# Sheet2_Lab08.net
KiCad netlist of a schematic drawn in Altium Designer
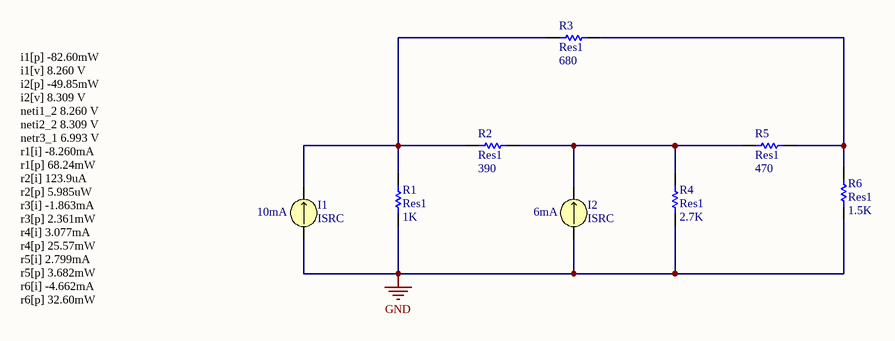
[diagram p0: Sheet2_Lab08.SchDoc]

(export (version "E")
  (design (tool "Eeschema 10.0.6"))
  (components
    (comp (ref "I1")
      (value "ISRC")
      (description "Current Source")
      (fields (field (name "ALTIUM_VALUE") "10mA") (field (name "PUBLISHER") "Altium Limited"))
      (libsource (lib "Simulation Sources") (part "ISRC"))
    )
    (comp (ref "I2")
      (value "ISRC")
      (description "Current Source")
      (fields (field (name "ALTIUM_VALUE") "6mA") (field (name "PUBLISHER") "Altium Limited"))
      (libsource (lib "Simulation Sources") (part "ISRC"))
    )
    (comp (ref "R1")
      (value "Res1")
      (footprint "AXIAL-0.3")
      (description "Resistor")
      (fields (field (name "ALTIUM_VALUE") "1K") (field (name "PUBLISHER") "Altium Limited"))
      (libsource (lib "Miscellaneous Devices") (part "Res1"))
    )
    (comp (ref "R2")
      (value "Res1")
      (footprint "AXIAL-0.3")
      (description "Resistor")
      (fields (field (name "ALTIUM_VALUE") "390") (field (name "PUBLISHER") "Altium Limited"))
      (libsource (lib "Miscellaneous Devices") (part "Res1"))
    )
    (comp (ref "R3")
      (value "Res1")
      (footprint "AXIAL-0.3")
      (description "Resistor")
      (fields (field (name "ALTIUM_VALUE") "680") (field (name "PUBLISHER") "Altium Limited"))
      (libsource (lib "Miscellaneous Devices") (part "Res1"))
    )
    (comp (ref "R4")
      (value "Res1")
      (footprint "AXIAL-0.3")
      (description "Resistor")
      (fields (field (name "ALTIUM_VALUE") "2.7K") (field (name "PUBLISHER") "Altium Limited"))
      (libsource (lib "Miscellaneous Devices") (part "Res1"))
    )
    (comp (ref "R5")
      (value "Res1")
      (footprint "AXIAL-0.3")
      (description "Resistor")
      (fields (field (name "ALTIUM_VALUE") "470") (field (name "PUBLISHER") "Altium Limited"))
      (libsource (lib "Miscellaneous Devices") (part "Res1"))
    )
    (comp (ref "R6")
      (value "Res1")
      (footprint "AXIAL-0.3")
      (description "Resistor")
      (fields (field (name "ALTIUM_VALUE") "1.5K") (field (name "PUBLISHER") "Altium Limited"))
      (libsource (lib "Miscellaneous Devices") (part "Res1"))
    )
  )
  (nets
    (net (code "1") (name "GND") (class "Default")
      (node (ref "I1") (pin "1") (pinfunction "1_1") (pintype "passive"))
      (node (ref "I2") (pin "1") (pinfunction "1_1") (pintype "passive"))
      (node (ref "R1") (pin "1") (pinfunction "1_1") (pintype "passive"))
      (node (ref "R4") (pin "2") (pinfunction "2_2") (pintype "passive"))
      (node (ref "R6") (pin "1") (pinfunction "1_1") (pintype "passive"))
    )
    (net (code "2") (name "Net-(I1-Pad2)") (class "Default")
      (node (ref "I1") (pin "2") (pinfunction "2_2") (pintype "passive"))
      (node (ref "R1") (pin "2") (pinfunction "2_2") (pintype "passive"))
      (node (ref "R2") (pin "2") (pinfunction "2_2") (pintype "passive"))
      (node (ref "R3") (pin "2") (pinfunction "2_2") (pintype "passive"))
    )
    (net (code "3") (name "Net-(I2-Pad2)") (class "Default")
      (node (ref "I2") (pin "2") (pinfunction "2_2") (pintype "passive"))
      (node (ref "R2") (pin "1") (pinfunction "1_1") (pintype "passive"))
      (node (ref "R4") (pin "1") (pinfunction "1_1") (pintype "passive"))
      (node (ref "R5") (pin "1") (pinfunction "1_1") (pintype "passive"))
    )
    (net (code "4") (name "Net-(R3-Pad1)") (class "Default")
      (node (ref "R3") (pin "1") (pinfunction "1_1") (pintype "passive"))
      (node (ref "R5") (pin "2") (pinfunction "2_2") (pintype "passive"))
      (node (ref "R6") (pin "2") (pinfunction "2_2") (pintype "passive"))
    )
  )
)
